# alim.net
KiCad netlist of a schematic drawn in Altium Designer
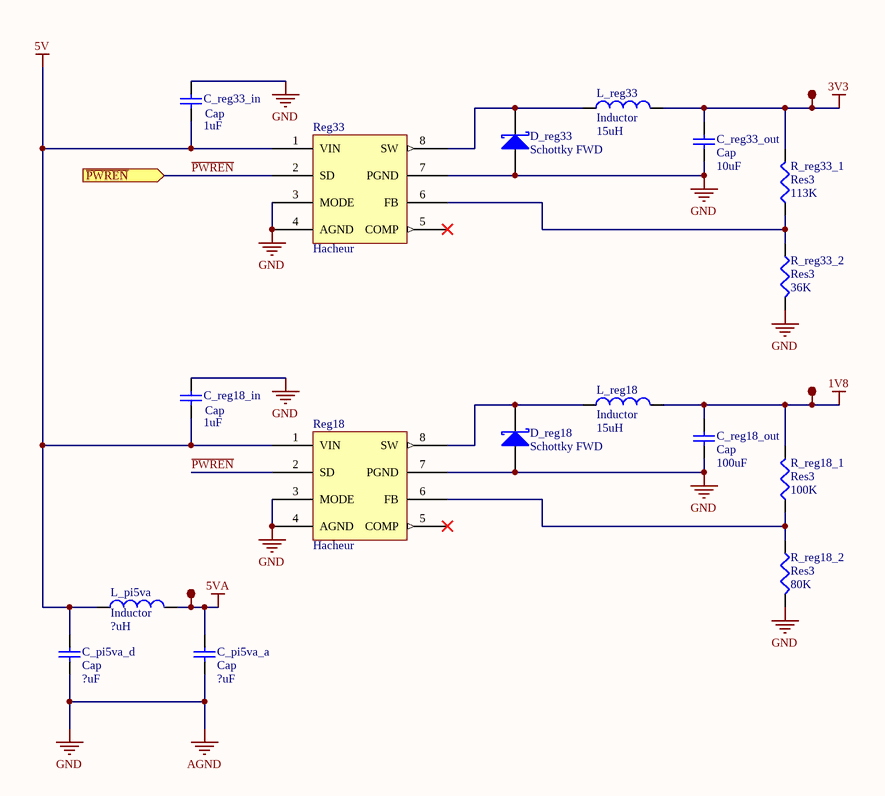
[diagram p0: alim.SchDoc]

(export (version "E")
  (design (tool "Eeschema 10.0.6"))
  (components
    (comp (ref "C_pi5va_a")
      (value "Cap")
      (footprint "ourprints:0805")
      (description "Capacitor")
      (fields (field (name "ALTIUM_VALUE") "?uF") (field (name "PUBLISHER") "Altium Limited"))
      (libsource (lib "Miscellaneous Devices") (part "Cap"))
    )
    (comp (ref "C_pi5va_d")
      (value "Cap")
      (footprint "ourprints:0805")
      (description "Capacitor")
      (fields (field (name "ALTIUM_VALUE") "?uF") (field (name "PUBLISHER") "Altium Limited"))
      (libsource (lib "Miscellaneous Devices") (part "Cap"))
    )
    (comp (ref "C_reg18_in")
      (value "Cap")
      (footprint "ourprints:0805")
      (description "Capacitor")
      (fields (field (name "ALTIUM_VALUE") "1uF") (field (name "PUBLISHER") "Altium Limited"))
      (libsource (lib "Miscellaneous Devices") (part "Cap"))
    )
    (comp (ref "C_reg18_out")
      (value "Cap")
      (footprint "ourprints:0805")
      (description "Capacitor")
      (fields (field (name "ALTIUM_VALUE") "100uF") (field (name "PUBLISHER") "Altium Limited"))
      (libsource (lib "Miscellaneous Devices") (part "Cap"))
    )
    (comp (ref "C_reg33_in")
      (value "Cap")
      (footprint "ourprints:0805")
      (description "Capacitor")
      (fields (field (name "ALTIUM_VALUE") "1uF") (field (name "PUBLISHER") "Altium Limited"))
      (libsource (lib "Miscellaneous Devices") (part "Cap"))
    )
    (comp (ref "C_reg33_out")
      (value "Cap")
      (footprint "ourprints:0805")
      (description "Capacitor")
      (fields (field (name "ALTIUM_VALUE") "10uF") (field (name "PUBLISHER") "Altium Limited"))
      (libsource (lib "Miscellaneous Devices") (part "Cap"))
    )
    (comp (ref "D_reg18")
      (value "Schottky FWD")
      (footprint "Diode")
      (description "Silicon RF Schottky Diode for Mixer Applications in the VHF/UHF Range")
      (fields (field (name "PUBLISHER") "Altium Limited"))
      (libsource (lib "Miscellaneous Devices") (part "Diode BAT17"))
    )
    (comp (ref "D_reg33")
      (value "Schottky FWD")
      (footprint "Diode")
      (description "Silicon RF Schottky Diode for Mixer Applications in the VHF/UHF Range")
      (fields (field (name "PUBLISHER") "Altium Limited"))
      (libsource (lib "Miscellaneous Devices") (part "Diode BAT17"))
    )
    (comp (ref "L_pi5va")
      (value "Inductor")
      (footprint "0805")
      (fields (field (name "ALTIUM_VALUE") "?uH") (field (name "PUBLISHER") "Altium Limited"))
      (libsource (lib "Miscellaneous Devices") (part "Inductor"))
    )
    (comp (ref "L_reg18")
      (value "Inductor")
      (footprint "ourprints:Bobine_alim")
      (fields (field (name "ALTIUM_VALUE") "15uH") (field (name "PUBLISHER") "Altium Limited"))
      (libsource (lib "Miscellaneous Devices") (part "Inductor"))
    )
    (comp (ref "L_reg33")
      (value "Inductor")
      (footprint "Bobine_alim")
      (fields (field (name "ALTIUM_VALUE") "15uH") (field (name "PUBLISHER") "Altium Limited"))
      (libsource (lib "Miscellaneous Devices") (part "Inductor"))
    )
    (comp (ref "Reg18") (value "Hacheur") (footprint "SOIC8_M") (libsource (lib "ourlibs") (part "Hacheur")))
    (comp (ref "Reg33") (value "Hacheur") (footprint "SOIC8_M") (libsource (lib "ourlibs") (part "Hacheur")))
    (comp (ref "R_reg18_1")
      (value "Res3")
      (footprint "ourprints:0805")
      (description "Resistor")
      (fields (field (name "ALTIUM_VALUE") "100K") (field (name "PUBLISHER") "Altium Limited"))
      (libsource (lib "Miscellaneous Devices") (part "Res3"))
    )
    (comp (ref "R_reg18_2")
      (value "Res3")
      (footprint "ourprints:0805")
      (description "Resistor")
      (fields (field (name "ALTIUM_VALUE") "80K") (field (name "PUBLISHER") "Altium Limited"))
      (libsource (lib "Miscellaneous Devices") (part "Res3"))
    )
    (comp (ref "R_reg33_1")
      (value "Res3")
      (footprint "ourprints:0805")
      (description "Resistor")
      (fields (field (name "ALTIUM_VALUE") "113K") (field (name "PUBLISHER") "Altium Limited"))
      (libsource (lib "Miscellaneous Devices") (part "Res3"))
    )
    (comp (ref "R_reg33_2")
      (value "Res3")
      (footprint "ourprints:0805")
      (description "Resistor")
      (fields (field (name "ALTIUM_VALUE") "36K") (field (name "PUBLISHER") "Altium Limited"))
      (libsource (lib "Miscellaneous Devices") (part "Res3"))
    )
    (comp (ref "TP_1v8")
      (value "TestPoint")
      (footprint "testpoint")
      (libsource (lib "ourlibs") (part "TestPoint"))
    )
    (comp (ref "TP_3v3")
      (value "TestPoint")
      (footprint "testpoint")
      (libsource (lib "ourlibs") (part "TestPoint"))
    )
    (comp (ref "TP_5va")
      (value "TestPoint")
      (footprint "testpoint")
      (libsource (lib "ourlibs") (part "TestPoint"))
    )
  )
  (nets
    (net (code "1") (name "/~{PWREN}") (class "Default")
      (node (ref "Reg18") (pin "2") (pinfunction "SD_2") (pintype "passive"))
      (node (ref "Reg33") (pin "2") (pinfunction "SD_2") (pintype "passive"))
    )
    (net (code "2") (name "1V8") (class "Default")
      (node (ref "C_reg18_out") (pin "1") (pinfunction "1_1") (pintype "passive"))
      (node (ref "L_reg18") (pin "2") (pinfunction "2_2") (pintype "passive"))
      (node (ref "R_reg18_1") (pin "2") (pinfunction "2_2") (pintype "passive"))
      (node (ref "TP_1v8") (pin "1") (pinfunction "TP_1") (pintype "passive"))
    )
    (net (code "3") (name "3V3") (class "Default")
      (node (ref "C_reg33_out") (pin "1") (pinfunction "1_1") (pintype "passive"))
      (node (ref "L_reg33") (pin "2") (pinfunction "2_2") (pintype "passive"))
      (node (ref "R_reg33_1") (pin "2") (pinfunction "2_2") (pintype "passive"))
      (node (ref "TP_3v3") (pin "1") (pinfunction "TP_1") (pintype "passive"))
    )
    (net (code "4") (name "5V") (class "Default")
      (node (ref "C_pi5va_d") (pin "1") (pinfunction "1_1") (pintype "passive"))
      (node (ref "C_reg18_in") (pin "2") (pinfunction "2_2") (pintype "passive"))
      (node (ref "C_reg33_in") (pin "2") (pinfunction "2_2") (pintype "passive"))
      (node (ref "L_pi5va") (pin "1") (pinfunction "1_1") (pintype "passive"))
      (node (ref "Reg18") (pin "1") (pinfunction "VIN_1") (pintype "power_in"))
      (node (ref "Reg33") (pin "1") (pinfunction "VIN_1") (pintype "power_in"))
    )
    (net (code "5") (name "5VA") (class "Default")
      (node (ref "C_pi5va_a") (pin "1") (pinfunction "1_1") (pintype "passive"))
      (node (ref "L_pi5va") (pin "2") (pinfunction "2_2") (pintype "passive"))
      (node (ref "TP_5va") (pin "1") (pinfunction "TP_1") (pintype "passive"))
    )
    (net (code "6") (name "AGND") (class "Default")
      (node (ref "C_pi5va_a") (pin "2") (pinfunction "2_2") (pintype "passive"))
      (node (ref "C_pi5va_d") (pin "2") (pinfunction "2_2") (pintype "passive"))
      (node (ref "C_reg18_in") (pin "1") (pinfunction "1_1") (pintype "passive"))
      (node (ref "C_reg18_out") (pin "2") (pinfunction "2_2") (pintype "passive"))
      (node (ref "C_reg33_in") (pin "1") (pinfunction "1_1") (pintype "passive"))
      (node (ref "C_reg33_out") (pin "2") (pinfunction "2_2") (pintype "passive"))
      (node (ref "D_reg18") (pin "1") (pinfunction "A_1") (pintype "passive"))
      (node (ref "D_reg33") (pin "1") (pinfunction "A_1") (pintype "passive"))
      (node (ref "R_reg18_2") (pin "2") (pinfunction "2_2") (pintype "passive"))
      (node (ref "R_reg33_2") (pin "2") (pinfunction "2_2") (pintype "passive"))
      (node (ref "Reg18") (pin "3") (pinfunction "MODE_3") (pintype "passive"))
      (node (ref "Reg18") (pin "4") (pinfunction "AGND_4") (pintype "power_in"))
      (node (ref "Reg18") (pin "7") (pinfunction "PGND_7") (pintype "power_in"))
      (node (ref "Reg33") (pin "3") (pinfunction "MODE_3") (pintype "passive"))
      (node (ref "Reg33") (pin "4") (pinfunction "AGND_4") (pintype "power_in"))
      (node (ref "Reg33") (pin "7") (pinfunction "PGND_7") (pintype "power_in"))
    )
    (net (code "7") (name "Net-(D_reg18-K)") (class "Default")
      (node (ref "D_reg18") (pin "2") (pinfunction "K_2") (pintype "passive"))
      (node (ref "L_reg18") (pin "1") (pinfunction "1_1") (pintype "passive"))
      (node (ref "Reg18") (pin "8") (pinfunction "SW_8") (pintype "output"))
    )
    (net (code "8") (name "Net-(D_reg33-K)") (class "Default")
      (node (ref "D_reg33") (pin "2") (pinfunction "K_2") (pintype "passive"))
      (node (ref "L_reg33") (pin "1") (pinfunction "1_1") (pintype "passive"))
      (node (ref "Reg33") (pin "8") (pinfunction "SW_8") (pintype "output"))
    )
    (net (code "9") (name "Net-(Reg18-FB)") (class "Default")
      (node (ref "R_reg18_1") (pin "1") (pinfunction "1_1") (pintype "passive"))
      (node (ref "R_reg18_2") (pin "1") (pinfunction "1_1") (pintype "passive"))
      (node (ref "Reg18") (pin "6") (pinfunction "FB_6") (pintype "passive"))
    )
    (net (code "10") (name "Net-(Reg33-FB)") (class "Default")
      (node (ref "R_reg33_1") (pin "1") (pinfunction "1_1") (pintype "passive"))
      (node (ref "R_reg33_2") (pin "1") (pinfunction "1_1") (pintype "passive"))
      (node (ref "Reg33") (pin "6") (pinfunction "FB_6") (pintype "passive"))
    )
    (net (code "11") (name "unconnected-(Reg18-COMP-Pad5)") (class "Default")
      (node (ref "Reg18") (pin "5") (pinfunction "COMP_5") (pintype "output+no_connect"))
    )
    (net (code "12") (name "unconnected-(Reg33-COMP-Pad5)") (class "Default")
      (node (ref "Reg33") (pin "5") (pinfunction "COMP_5") (pintype "output+no_connect"))
    )
  )
)
